# 2_Analog.net
KiCad netlist of a schematic drawn in Altium Designer
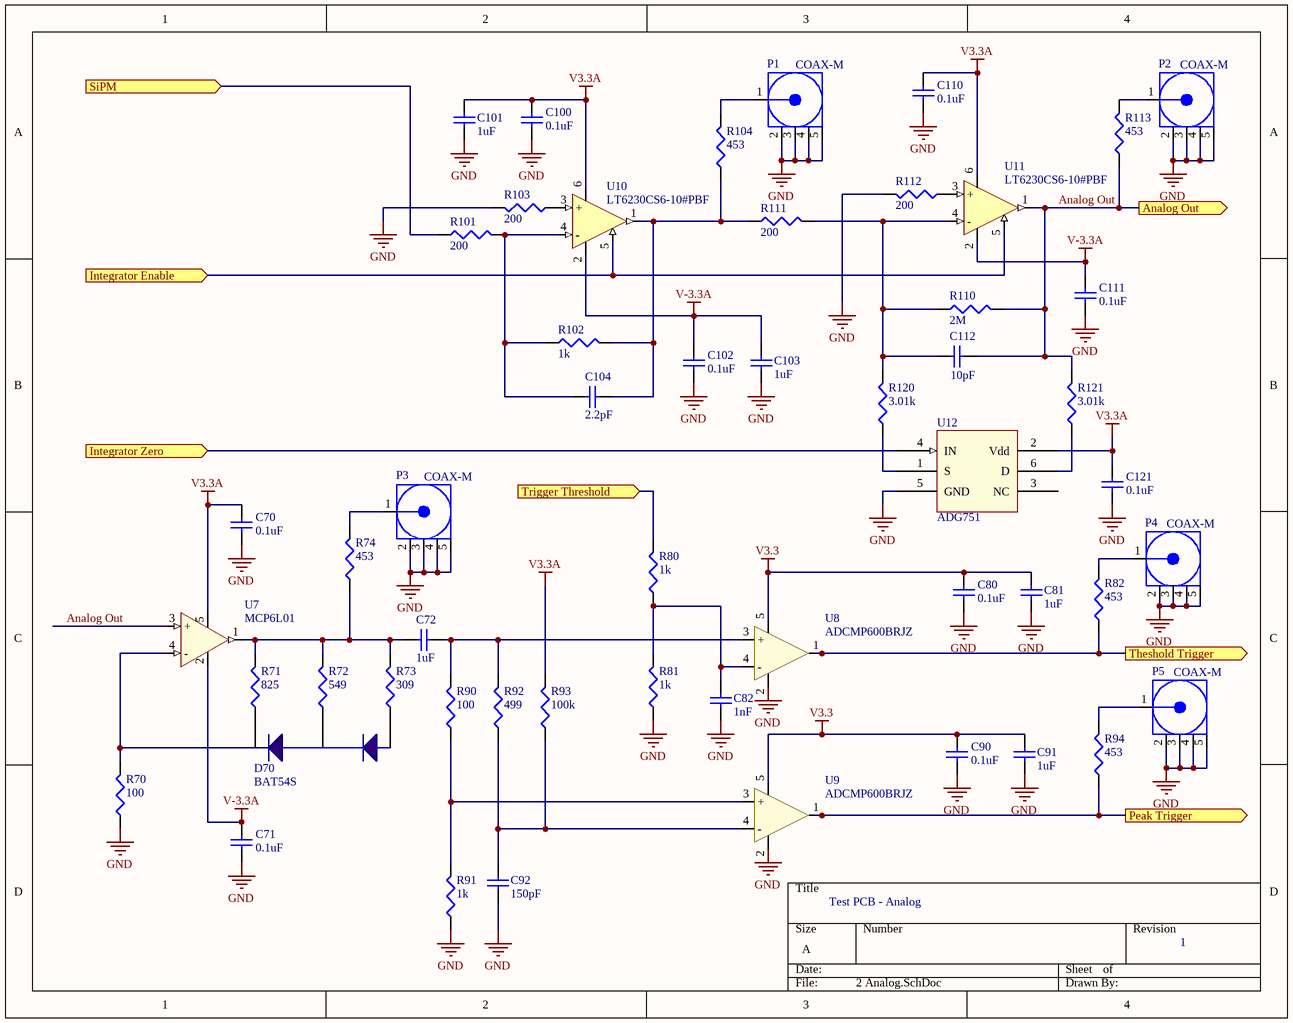
[diagram p0: 2 Analog.SchDoc]

(export (version "E")
  (design (tool "Eeschema 10.0.6"))
  (components
    (comp (ref "C70")
      (value "0.1uF")
      (footprint "C0402")
      (description "Capacitor, SM")
      (fields (field (name "PUBLISHER") "Altium Limited"))
      (libsource (lib "Graylark") (part "Cap SM"))
    )
    (comp (ref "C71")
      (value "0.1uF")
      (footprint "C0402")
      (description "Capacitor, SM")
      (fields (field (name "PUBLISHER") "Altium Limited"))
      (libsource (lib "Graylark") (part "Cap SM"))
    )
    (comp (ref "C72")
      (value "1uF")
      (footprint "C0603")
      (description "Capacitor, SM")
      (fields (field (name "PUBLISHER") "Altium Limited"))
      (libsource (lib "Graylark") (part "Cap SM"))
    )
    (comp (ref "C80")
      (value "0.1uF")
      (footprint "C0402")
      (description "Capacitor, SM")
      (fields (field (name "PUBLISHER") "Altium Limited"))
      (libsource (lib "Graylark") (part "Cap SM"))
    )
    (comp (ref "C81")
      (value "1uF")
      (footprint "C0603")
      (description "Capacitor, SM")
      (fields (field (name "PUBLISHER") "Altium Limited"))
      (libsource (lib "Graylark") (part "Cap SM"))
    )
    (comp (ref "C82")
      (value "1nF")
      (footprint "C0603")
      (description "Capacitor, SM")
      (fields (field (name "PUBLISHER") "Altium Limited"))
      (libsource (lib "Graylark") (part "Cap SM"))
    )
    (comp (ref "C90")
      (value "0.1uF")
      (footprint "C0402")
      (description "Capacitor, SM")
      (fields (field (name "PUBLISHER") "Altium Limited"))
      (libsource (lib "Graylark") (part "Cap SM"))
    )
    (comp (ref "C91")
      (value "1uF")
      (footprint "C0603")
      (description "Capacitor, SM")
      (fields (field (name "PUBLISHER") "Altium Limited"))
      (libsource (lib "Graylark") (part "Cap SM"))
    )
    (comp (ref "C92")
      (value "150pF")
      (footprint "C0603")
      (description "Capacitor, SM")
      (fields (field (name "PUBLISHER") "Altium Limited"))
      (libsource (lib "Graylark") (part "Cap SM"))
    )
    (comp (ref "C100")
      (value "0.1uF")
      (footprint "C0402")
      (description "Capacitor, SM")
      (fields (field (name "PUBLISHER") "Altium Limited"))
      (libsource (lib "Graylark") (part "Cap SM"))
    )
    (comp (ref "C101")
      (value "1uF")
      (footprint "C0603")
      (description "Capacitor, SM")
      (fields (field (name "PUBLISHER") "Altium Limited"))
      (libsource (lib "Graylark") (part "Cap SM"))
    )
    (comp (ref "C102")
      (value "0.1uF")
      (footprint "C0402")
      (description "Capacitor, SM")
      (fields (field (name "PUBLISHER") "Altium Limited"))
      (libsource (lib "Graylark") (part "Cap SM"))
    )
    (comp (ref "C103")
      (value "1uF")
      (footprint "C0603")
      (description "Capacitor, SM")
      (fields (field (name "PUBLISHER") "Altium Limited"))
      (libsource (lib "Graylark") (part "Cap SM"))
    )
    (comp (ref "C104")
      (value "2.2pF")
      (footprint "C0603")
      (description "Capacitor, SM")
      (fields (field (name "PUBLISHER") "Altium Limited"))
      (libsource (lib "Graylark") (part "Cap SM"))
    )
    (comp (ref "C110")
      (value "0.1uF")
      (footprint "C0402")
      (description "Capacitor, SM")
      (fields (field (name "PUBLISHER") "Altium Limited"))
      (libsource (lib "Graylark") (part "Cap SM"))
    )
    (comp (ref "C111")
      (value "0.1uF")
      (footprint "C0402")
      (description "Capacitor, SM")
      (fields (field (name "PUBLISHER") "Altium Limited"))
      (libsource (lib "Graylark") (part "Cap SM"))
    )
    (comp (ref "C112")
      (value "10pF")
      (footprint "C0603")
      (description "Capacitor, SM")
      (fields (field (name "PUBLISHER") "Altium Limited"))
      (libsource (lib "Graylark") (part "Cap SM"))
    )
    (comp (ref "C121")
      (value "0.1uF")
      (footprint "C0402")
      (description "Capacitor, SM")
      (fields (field (name "PUBLISHER") "Altium Limited"))
      (libsource (lib "Graylark") (part "Cap SM"))
    )
    (comp (ref "D70") (value "BAT54S") (footprint "SOT323-3") (libsource (lib "Graylark") (part "BAT54S")))
    (comp (ref "P1")
      (value "COAX-M")
      (footprint "MMCX/SM")
      (description "RF Coaxial PCB Connector, MMCX; Thru-Hole, Vertical Mount Plug,  50 Ohm Impedance")
      (fields (field (name "PUBLISHER") "Altium Limited"))
      (libsource (lib "Graylark") (part "COAX-M"))
    )
    (comp (ref "P2")
      (value "COAX-M")
      (footprint "MMCX/SM")
      (description "RF Coaxial PCB Connector, MMCX; Thru-Hole, Vertical Mount Plug,  50 Ohm Impedance")
      (fields (field (name "PUBLISHER") "Altium Limited"))
      (libsource (lib "Graylark") (part "COAX-M"))
    )
    (comp (ref "P3")
      (value "COAX-M")
      (footprint "MMCX/SM")
      (description "RF Coaxial PCB Connector, MMCX; Thru-Hole, Vertical Mount Plug,  50 Ohm Impedance")
      (fields (field (name "PUBLISHER") "Altium Limited"))
      (libsource (lib "Graylark") (part "COAX-M"))
    )
    (comp (ref "P4")
      (value "COAX-M")
      (footprint "MMCX/SM")
      (description "RF Coaxial PCB Connector, MMCX; Thru-Hole, Vertical Mount Plug,  50 Ohm Impedance")
      (fields (field (name "PUBLISHER") "Altium Limited"))
      (libsource (lib "Graylark") (part "COAX-M"))
    )
    (comp (ref "P5")
      (value "COAX-M")
      (footprint "MMCX/SM")
      (description "RF Coaxial PCB Connector, MMCX; Thru-Hole, Vertical Mount Plug,  50 Ohm Impedance")
      (fields (field (name "PUBLISHER") "Altium Limited"))
      (libsource (lib "Graylark") (part "COAX-M"))
    )
    (comp (ref "R70")
      (value "100")
      (footprint "R0603")
      (description "Resistor")
      (fields (field (name "PUBLISHER") "Altium Limited"))
      (libsource (lib "Graylark") (part "Res SM"))
    )
    (comp (ref "R71")
      (value "825")
      (footprint "R0603")
      (description "Resistor")
      (fields (field (name "PUBLISHER") "Altium Limited"))
      (libsource (lib "Graylark") (part "Res SM"))
    )
    (comp (ref "R72")
      (value "549")
      (footprint "R0603")
      (description "Resistor")
      (fields (field (name "PUBLISHER") "Altium Limited"))
      (libsource (lib "Graylark") (part "Res SM"))
    )
    (comp (ref "R73")
      (value "309")
      (footprint "R0603")
      (description "Resistor")
      (fields (field (name "PUBLISHER") "Altium Limited"))
      (libsource (lib "Graylark") (part "Res SM"))
    )
    (comp (ref "R74")
      (value "453")
      (footprint "R0603")
      (description "Resistor")
      (fields (field (name "PUBLISHER") "Altium Limited"))
      (libsource (lib "Graylark") (part "Res SM"))
    )
    (comp (ref "R80")
      (value "1k")
      (footprint "R0603")
      (description "Resistor")
      (fields (field (name "PUBLISHER") "Altium Limited"))
      (libsource (lib "Graylark") (part "Res SM"))
    )
    (comp (ref "R81")
      (value "1k")
      (footprint "R0603")
      (description "Resistor")
      (fields (field (name "PUBLISHER") "Altium Limited"))
      (libsource (lib "Graylark") (part "Res SM"))
    )
    (comp (ref "R82")
      (value "453")
      (footprint "R0603")
      (description "Resistor")
      (fields (field (name "PUBLISHER") "Altium Limited"))
      (libsource (lib "Graylark") (part "Res SM"))
    )
    (comp (ref "R90")
      (value "100")
      (footprint "R0603")
      (description "Resistor")
      (fields (field (name "PUBLISHER") "Altium Limited"))
      (libsource (lib "Graylark") (part "Res SM"))
    )
    (comp (ref "R91")
      (value "1k")
      (footprint "R0603")
      (description "Resistor")
      (fields (field (name "PUBLISHER") "Altium Limited"))
      (libsource (lib "Graylark") (part "Res SM"))
    )
    (comp (ref "R92")
      (value "499")
      (footprint "R0603")
      (description "Resistor")
      (fields (field (name "PUBLISHER") "Altium Limited"))
      (libsource (lib "Graylark") (part "Res SM"))
    )
    (comp (ref "R93")
      (value "100k")
      (footprint "R0603")
      (description "Resistor")
      (fields (field (name "PUBLISHER") "Altium Limited"))
      (libsource (lib "Graylark") (part "Res SM"))
    )
    (comp (ref "R94")
      (value "453")
      (footprint "R0603")
      (description "Resistor")
      (fields (field (name "PUBLISHER") "Altium Limited"))
      (libsource (lib "Graylark") (part "Res SM"))
    )
    (comp (ref "R101")
      (value "200")
      (footprint "R0603")
      (description "Resistor")
      (fields (field (name "PUBLISHER") "Altium Limited"))
      (libsource (lib "Graylark") (part "Res SM"))
    )
    (comp (ref "R102")
      (value "1k")
      (footprint "R0603")
      (description "Resistor")
      (fields (field (name "PUBLISHER") "Altium Limited"))
      (libsource (lib "Graylark") (part "Res SM"))
    )
    (comp (ref "R103")
      (value "200")
      (footprint "R0603")
      (description "Resistor")
      (fields (field (name "PUBLISHER") "Altium Limited"))
      (libsource (lib "Graylark") (part "Res SM"))
    )
    (comp (ref "R104")
      (value "453")
      (footprint "R0603")
      (description "Resistor")
      (fields (field (name "PUBLISHER") "Altium Limited"))
      (libsource (lib "Graylark") (part "Res SM"))
    )
    (comp (ref "R110")
      (value "2M")
      (footprint "R0603")
      (description "Resistor")
      (fields (field (name "PUBLISHER") "Altium Limited"))
      (libsource (lib "Graylark") (part "Res SM"))
    )
    (comp (ref "R111")
      (value "200")
      (footprint "R0603")
      (description "Resistor")
      (fields (field (name "PUBLISHER") "Altium Limited"))
      (libsource (lib "Graylark") (part "Res SM"))
    )
    (comp (ref "R112")
      (value "200")
      (footprint "R0603")
      (description "Resistor")
      (fields (field (name "PUBLISHER") "Altium Limited"))
      (libsource (lib "Graylark") (part "Res SM"))
    )
    (comp (ref "R113")
      (value "453")
      (footprint "R0603")
      (description "Resistor")
      (fields (field (name "PUBLISHER") "Altium Limited"))
      (libsource (lib "Graylark") (part "Res SM"))
    )
    (comp (ref "R120")
      (value "3.01k")
      (footprint "R0603")
      (description "Resistor")
      (fields (field (name "PUBLISHER") "Altium Limited"))
      (libsource (lib "Graylark") (part "Res SM"))
    )
    (comp (ref "R121")
      (value "3.01k")
      (footprint "R0603")
      (description "Resistor")
      (fields (field (name "PUBLISHER") "Altium Limited"))
      (libsource (lib "Graylark") (part "Res SM"))
    )
    (comp (ref "U7")
      (value "MCP6L01")
      (footprint "SOT23-5")
      (description "Op amp RRIO")
      (libsource (lib "Graylark") (part "MCP6L01"))
    )
    (comp (ref "U8")
      (value "ADCMP600BRJZ")
      (footprint "SC70-5")
      (description "Comparator")
      (libsource (lib "Graylark") (part "ADCMP600"))
    )
    (comp (ref "U9")
      (value "ADCMP600BRJZ")
      (footprint "SC70-5")
      (description "Comparator")
      (libsource (lib "Graylark") (part "ADCMP600"))
    )
    (comp (ref "U10")
      (value "LT6230CS6-10#PBF")
      (footprint "SOT23-6")
      (description "Op amp, RRO")
      (libsource (lib "Graylark") (part "LMH6639"))
    )
    (comp (ref "U11")
      (value "LT6230CS6-10#PBF")
      (footprint "SOT23-6")
      (description "Op amp, RRO")
      (libsource (lib "Graylark") (part "LMH6639"))
    )
    (comp (ref "U12") (value "ADG751") (footprint "SOT23-6") (libsource (lib "Graylark") (part "ADG751")))
  )
  (nets
    (net (code "1") (name "/Analog Out") (class "Default")
      (node (ref "C112") (pin "2") (pinfunction "2_2") (pintype "passive"))
      (node (ref "R110") (pin "2") (pinfunction "2_2") (pintype "passive"))
      (node (ref "R113") (pin "1") (pinfunction "1_1") (pintype "passive"))
      (node (ref "R121") (pin "2") (pinfunction "2_2") (pintype "passive"))
      (node (ref "U11") (pin "1") (pinfunction "Output_1") (pintype "output"))
      (node (ref "U7") (pin "3") (pinfunction "+_3") (pintype "input"))
    )
    (net (code "2") (name "/Integrator Enable") (class "Default")
      (node (ref "U10") (pin "5") (pinfunction "/S/D_5") (pintype "input"))
      (node (ref "U11") (pin "5") (pinfunction "/S/D_5") (pintype "input"))
    )
    (net (code "3") (name "/Integrator Zero") (class "Default")
      (node (ref "U12") (pin "4") (pinfunction "IN_4") (pintype "input"))
    )
    (net (code "4") (name "/Peak Trigger") (class "Default")
      (node (ref "R94") (pin "1") (pinfunction "1_1") (pintype "passive"))
      (node (ref "U9") (pin "1") (pinfunction "Q_1") (pintype "passive"))
    )
    (net (code "5") (name "/SiPM") (class "Default")
      (node (ref "R101") (pin "1") (pinfunction "1_1") (pintype "passive"))
    )
    (net (code "6") (name "/Theshold Trigger") (class "Default")
      (node (ref "R82") (pin "1") (pinfunction "1_1") (pintype "passive"))
      (node (ref "U8") (pin "1") (pinfunction "Q_1") (pintype "passive"))
    )
    (net (code "7") (name "/Trigger Threshold") (class "Default")
      (node (ref "R80") (pin "2") (pinfunction "2_2") (pintype "passive"))
    )
    (net (code "8") (name "GND") (class "Default")
      (node (ref "C100") (pin "1") (pinfunction "1_1") (pintype "passive"))
      (node (ref "C101") (pin "1") (pinfunction "1_1") (pintype "passive"))
      (node (ref "C102") (pin "1") (pinfunction "1_1") (pintype "passive"))
      (node (ref "C103") (pin "1") (pinfunction "1_1") (pintype "passive"))
      (node (ref "C110") (pin "1") (pinfunction "1_1") (pintype "passive"))
      (node (ref "C111") (pin "1") (pinfunction "1_1") (pintype "passive"))
      (node (ref "C121") (pin "1") (pinfunction "1_1") (pintype "passive"))
      (node (ref "C70") (pin "1") (pinfunction "1_1") (pintype "passive"))
      (node (ref "C71") (pin "1") (pinfunction "1_1") (pintype "passive"))
      (node (ref "C80") (pin "1") (pinfunction "1_1") (pintype "passive"))
      (node (ref "C81") (pin "1") (pinfunction "1_1") (pintype "passive"))
      (node (ref "C82") (pin "1") (pinfunction "1_1") (pintype "passive"))
      (node (ref "C90") (pin "1") (pinfunction "1_1") (pintype "passive"))
      (node (ref "C91") (pin "1") (pinfunction "1_1") (pintype "passive"))
      (node (ref "C92") (pin "1") (pinfunction "1_1") (pintype "passive"))
      (node (ref "P1") (pin "2") (pinfunction "GND_2") (pintype "power_in"))
      (node (ref "P1") (pin "3") (pinfunction "GND_3") (pintype "power_in"))
      (node (ref "P1") (pin "4") (pinfunction "GND_4") (pintype "power_in"))
      (node (ref "P1") (pin "5") (pinfunction "GND_5") (pintype "power_in"))
      (node (ref "P2") (pin "2") (pinfunction "GND_2") (pintype "power_in"))
      (node (ref "P2") (pin "3") (pinfunction "GND_3") (pintype "power_in"))
      (node (ref "P2") (pin "4") (pinfunction "GND_4") (pintype "power_in"))
      (node (ref "P2") (pin "5") (pinfunction "GND_5") (pintype "power_in"))
      (node (ref "P3") (pin "2") (pinfunction "GND_2") (pintype "power_in"))
      (node (ref "P3") (pin "3") (pinfunction "GND_3") (pintype "power_in"))
      (node (ref "P3") (pin "4") (pinfunction "GND_4") (pintype "power_in"))
      (node (ref "P3") (pin "5") (pinfunction "GND_5") (pintype "power_in"))
      (node (ref "P4") (pin "2") (pinfunction "GND_2") (pintype "power_in"))
      (node (ref "P4") (pin "3") (pinfunction "GND_3") (pintype "power_in"))
      (node (ref "P4") (pin "4") (pinfunction "GND_4") (pintype "power_in"))
      (node (ref "P4") (pin "5") (pinfunction "GND_5") (pintype "power_in"))
      (node (ref "P5") (pin "2") (pinfunction "GND_2") (pintype "power_in"))
      (node (ref "P5") (pin "3") (pinfunction "GND_3") (pintype "power_in"))
      (node (ref "P5") (pin "4") (pinfunction "GND_4") (pintype "power_in"))
      (node (ref "P5") (pin "5") (pinfunction "GND_5") (pintype "power_in"))
      (node (ref "R103") (pin "2") (pinfunction "2_2") (pintype "passive"))
      (node (ref "R112") (pin "2") (pinfunction "2_2") (pintype "passive"))
      (node (ref "R70") (pin "1") (pinfunction "1_1") (pintype "passive"))
      (node (ref "R81") (pin "1") (pinfunction "1_1") (pintype "passive"))
      (node (ref "R91") (pin "1") (pinfunction "1_1") (pintype "passive"))
      (node (ref "U12") (pin "5") (pinfunction "GND_5") (pintype "power_in"))
      (node (ref "U8") (pin "2") (pinfunction "GND_2") (pintype "power_in"))
      (node (ref "U9") (pin "2") (pinfunction "GND_2") (pintype "power_in"))
    )
    (net (code "9") (name "Net-(D70-Pad1)") (class "Default")
      (node (ref "D70") (pin "1") (pinfunction "1_1") (pintype "passive"))
      (node (ref "R73") (pin "1") (pinfunction "1_1") (pintype "passive"))
    )
    (net (code "10") (name "Net-(D70-Pad2)") (class "Default")
      (node (ref "D70") (pin "2") (pinfunction "2_2") (pintype "passive"))
      (node (ref "R71") (pin "1") (pinfunction "1_1") (pintype "passive"))
    )
    (net (code "11") (name "Net-(D70-Pad3)") (class "Default")
      (node (ref "D70") (pin "3") (pinfunction "3_3") (pintype "passive"))
      (node (ref "R72") (pin "1") (pinfunction "1_1") (pintype "passive"))
    )
    (net (code "12") (name "Net-(P1-Signal)") (class "Default")
      (node (ref "P1") (pin "1") (pinfunction "Signal_1") (pintype "passive"))
      (node (ref "R104") (pin "2") (pinfunction "2_2") (pintype "passive"))
    )
    (net (code "13") (name "Net-(P2-Signal)") (class "Default")
      (node (ref "P2") (pin "1") (pinfunction "Signal_1") (pintype "passive"))
      (node (ref "R113") (pin "2") (pinfunction "2_2") (pintype "passive"))
    )
    (net (code "14") (name "Net-(P3-Signal)") (class "Default")
      (node (ref "P3") (pin "1") (pinfunction "Signal_1") (pintype "passive"))
      (node (ref "R74") (pin "2") (pinfunction "2_2") (pintype "passive"))
    )
    (net (code "15") (name "Net-(P4-Signal)") (class "Default")
      (node (ref "P4") (pin "1") (pinfunction "Signal_1") (pintype "passive"))
      (node (ref "R82") (pin "2") (pinfunction "2_2") (pintype "passive"))
    )
    (net (code "16") (name "Net-(P5-Signal)") (class "Default")
      (node (ref "P5") (pin "1") (pinfunction "Signal_1") (pintype "passive"))
      (node (ref "R94") (pin "2") (pinfunction "2_2") (pintype "passive"))
    )
    (net (code "17") (name "Net-(U7--)") (class "Default")
      (node (ref "R70") (pin "2") (pinfunction "2_2") (pintype "passive"))
      (node (ref "U7") (pin "4") (pinfunction "-_4") (pintype "input"))
    )
    (net (code "18") (name "Net-(U7-Vout)") (class "Default")
      (node (ref "C72") (pin "2") (pinfunction "2_2") (pintype "passive"))
      (node (ref "R71") (pin "2") (pinfunction "2_2") (pintype "passive"))
      (node (ref "R72") (pin "2") (pinfunction "2_2") (pintype "passive"))
      (node (ref "R73") (pin "2") (pinfunction "2_2") (pintype "passive"))
      (node (ref "R74") (pin "1") (pinfunction "1_1") (pintype "passive"))
      (node (ref "U7") (pin "1") (pinfunction "Vout_1") (pintype "output"))
    )
    (net (code "19") (name "Net-(U8-+)") (class "Default")
      (node (ref "C72") (pin "1") (pinfunction "1_1") (pintype "passive"))
      (node (ref "R90") (pin "2") (pinfunction "2_2") (pintype "passive"))
      (node (ref "R92") (pin "2") (pinfunction "2_2") (pintype "passive"))
      (node (ref "U8") (pin "3") (pinfunction "+_3") (pintype "passive"))
    )
    (net (code "20") (name "Net-(U8--)") (class "Default")
      (node (ref "C82") (pin "2") (pinfunction "2_2") (pintype "passive"))
      (node (ref "R80") (pin "1") (pinfunction "1_1") (pintype "passive"))
      (node (ref "R81") (pin "2") (pinfunction "2_2") (pintype "passive"))
      (node (ref "U8") (pin "4") (pinfunction "-_4") (pintype "passive"))
    )
    (net (code "21") (name "Net-(U9-+)") (class "Default")
      (node (ref "R90") (pin "1") (pinfunction "1_1") (pintype "passive"))
      (node (ref "R91") (pin "2") (pinfunction "2_2") (pintype "passive"))
      (node (ref "U9") (pin "3") (pinfunction "+_3") (pintype "passive"))
    )
    (net (code "22") (name "Net-(U9--)") (class "Default")
      (node (ref "C92") (pin "2") (pinfunction "2_2") (pintype "passive"))
      (node (ref "R92") (pin "1") (pinfunction "1_1") (pintype "passive"))
      (node (ref "R93") (pin "1") (pinfunction "1_1") (pintype "passive"))
      (node (ref "U9") (pin "4") (pinfunction "-_4") (pintype "passive"))
    )
    (net (code "23") (name "Net-(U10-+)") (class "Default")
      (node (ref "R103") (pin "1") (pinfunction "1_1") (pintype "passive"))
      (node (ref "U10") (pin "3") (pinfunction "+_3") (pintype "input"))
    )
    (net (code "24") (name "Net-(U10--)") (class "Default")
      (node (ref "C104") (pin "1") (pinfunction "1_1") (pintype "passive"))
      (node (ref "R101") (pin "2") (pinfunction "2_2") (pintype "passive"))
      (node (ref "R102") (pin "1") (pinfunction "1_1") (pintype "passive"))
      (node (ref "U10") (pin "4") (pinfunction "-_4") (pintype "input"))
    )
    (net (code "25") (name "Net-(U10-Output)") (class "Default")
      (node (ref "C104") (pin "2") (pinfunction "2_2") (pintype "passive"))
      (node (ref "R102") (pin "2") (pinfunction "2_2") (pintype "passive"))
      (node (ref "R104") (pin "1") (pinfunction "1_1") (pintype "passive"))
      (node (ref "R111") (pin "1") (pinfunction "1_1") (pintype "passive"))
      (node (ref "U10") (pin "1") (pinfunction "Output_1") (pintype "output"))
    )
    (net (code "26") (name "Net-(U11-+)") (class "Default")
      (node (ref "R112") (pin "1") (pinfunction "1_1") (pintype "passive"))
      (node (ref "U11") (pin "3") (pinfunction "+_3") (pintype "input"))
    )
    (net (code "27") (name "Net-(U11--)") (class "Default")
      (node (ref "C112") (pin "1") (pinfunction "1_1") (pintype "passive"))
      (node (ref "R110") (pin "1") (pinfunction "1_1") (pintype "passive"))
      (node (ref "R111") (pin "2") (pinfunction "2_2") (pintype "passive"))
      (node (ref "R120") (pin "2") (pinfunction "2_2") (pintype "passive"))
      (node (ref "U11") (pin "4") (pinfunction "-_4") (pintype "input"))
    )
    (net (code "28") (name "Net-(U12-D)") (class "Default")
      (node (ref "R121") (pin "1") (pinfunction "1_1") (pintype "passive"))
      (node (ref "U12") (pin "6") (pinfunction "D_6") (pintype "passive"))
    )
    (net (code "29") (name "Net-(U12-S)") (class "Default")
      (node (ref "R120") (pin "1") (pinfunction "1_1") (pintype "passive"))
      (node (ref "U12") (pin "1") (pinfunction "S_1") (pintype "passive"))
    )
    (net (code "30") (name "V-3.3A") (class "Default")
      (node (ref "C102") (pin "2") (pinfunction "2_2") (pintype "passive"))
      (node (ref "C103") (pin "2") (pinfunction "2_2") (pintype "passive"))
      (node (ref "C111") (pin "2") (pinfunction "2_2") (pintype "passive"))
      (node (ref "C71") (pin "2") (pinfunction "2_2") (pintype "passive"))
      (node (ref "U10") (pin "2") (pinfunction "V-_2") (pintype "power_in"))
      (node (ref "U11") (pin "2") (pinfunction "V-_2") (pintype "power_in"))
      (node (ref "U7") (pin "2") (pinfunction "GND_2") (pintype "power_in"))
    )
    (net (code "31") (name "V3.3") (class "Default")
      (node (ref "C80") (pin "2") (pinfunction "2_2") (pintype "passive"))
      (node (ref "C81") (pin "2") (pinfunction "2_2") (pintype "passive"))
      (node (ref "C90") (pin "2") (pinfunction "2_2") (pintype "passive"))
      (node (ref "C91") (pin "2") (pinfunction "2_2") (pintype "passive"))
      (node (ref "U8") (pin "5") (pinfunction "Vcc_5") (pintype "power_in"))
      (node (ref "U9") (pin "5") (pinfunction "Vcc_5") (pintype "power_in"))
    )
    (net (code "32") (name "V3.3A") (class "Default")
      (node (ref "C100") (pin "2") (pinfunction "2_2") (pintype "passive"))
      (node (ref "C101") (pin "2") (pinfunction "2_2") (pintype "passive"))
      (node (ref "C110") (pin "2") (pinfunction "2_2") (pintype "passive"))
      (node (ref "C121") (pin "2") (pinfunction "2_2") (pintype "passive"))
      (node (ref "C70") (pin "2") (pinfunction "2_2") (pintype "passive"))
      (node (ref "R93") (pin "2") (pinfunction "2_2") (pintype "passive"))
      (node (ref "U10") (pin "6") (pinfunction "V+_6") (pintype "power_in"))
      (node (ref "U11") (pin "6") (pinfunction "V+_6") (pintype "power_in"))
      (node (ref "U12") (pin "2") (pinfunction "Vdd_2") (pintype "power_in"))
      (node (ref "U7") (pin "5") (pinfunction "Vdd_5") (pintype "power_in"))
    )
    (net (code "33") (name "unconnected-(U12-NC-Pad3)") (class "Default")
      (node (ref "U12") (pin "3") (pinfunction "NC_3") (pintype "passive"))
    )
  )
)
